# stm32_schematic.net
KiCad netlist of a schematic drawn in Altium Designer
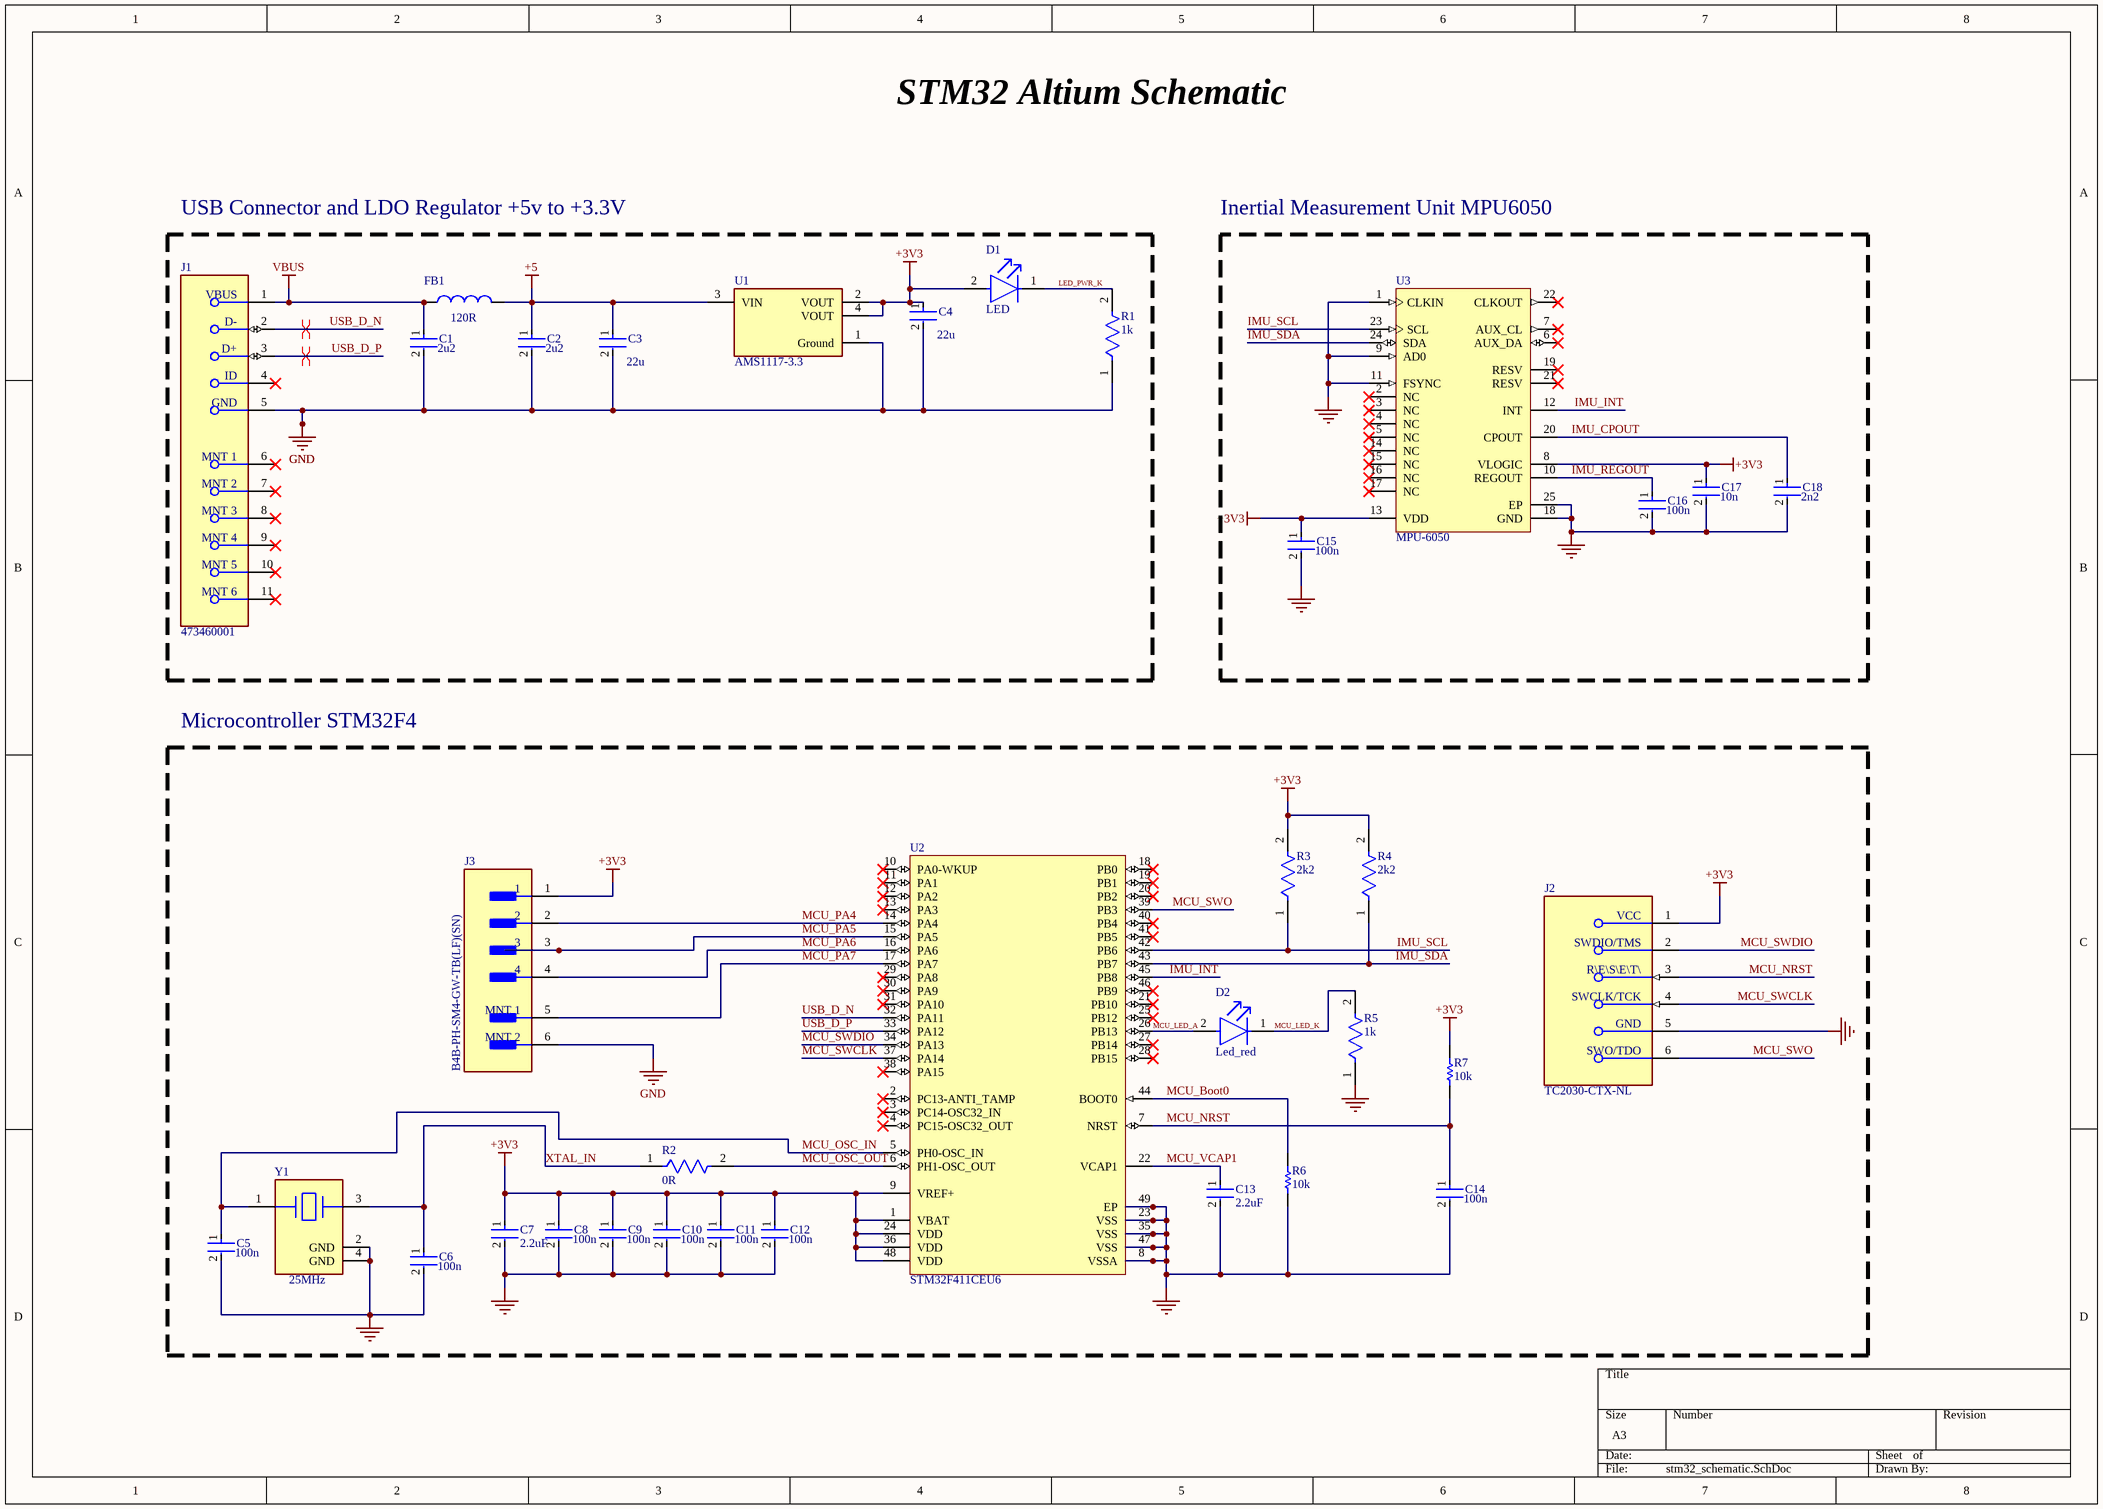
[diagram p0: stm32_schematic.SchDoc]

(export (version "E")
  (design (tool "Eeschema 10.0.6"))
  (components
    (comp (ref "C1")
      (value "2u2")
      (footprint "FP-CC0402-MFG")
      (description "CAP CER 1UF 16V X5R 0402")
      (fields
        (field (name "MANUFACTURER") "YAGEO")
        (field (name "OCTOPART") "https://octopart.com/cc0402krx5r7bb105-yageo-25629500")
      )
      (libsource (lib "Altium Content Vault") (part "11868f565c42a9108669ba33697ecf6"))
    )
    (comp (ref "C2")
      (value "2u2")
      (footprint "FP-CC0402-MFG")
      (description "CAP CER 1UF 16V X5R 0402")
      (fields
        (field (name "MANUFACTURER") "YAGEO")
        (field (name "OCTOPART") "https://octopart.com/cc0402krx5r7bb105-yageo-25629500")
      )
      (libsource (lib "Altium Content Vault") (part "11868f565c42a9108669ba33697ecf6"))
    )
    (comp (ref "C3")
      (value "22u")
      (footprint "FP-GRM21B-0_15-IPC_A")
      (description "Chip Multilayer Ceramic Capacitors for General Purpose, 0805, 4.7uF, X6S, 22%, 20%, 35V")
      (fields (field (name "TOLERANCE") "20%"))
      (libsource (lib "Altium Content Vault") (part "b4654b650e69147ec39a6b967a45e02"))
    )
    (comp (ref "C4")
      (value "22u")
      (footprint "FP-GRM21B-0_15-IPC_A")
      (description "Chip Multilayer Ceramic Capacitors for General Purpose, 0805, 4.7uF, X6S, 22%, 20%, 35V")
      (fields (field (name "TOLERANCE") "20%"))
      (libsource (lib "Altium Content Vault") (part "b4654b650e69147ec39a6b967a45e02"))
    )
    (comp (ref "C5")
      (value "100n")
      (footprint "FP-CC0402-MFG")
      (description "CAP CER 1UF 16V X5R 0402")
      (fields
        (field (name "MANUFACTURER") "YAGEO")
        (field (name "OCTOPART") "https://octopart.com/cc0402krx5r7bb105-yageo-25629500")
      )
      (libsource (lib "Altium Content Vault") (part "11868f565c42a9108669ba33697ecf6"))
    )
    (comp (ref "C6")
      (value "100n")
      (footprint "FP-CC0402-MFG")
      (description "CAP CER 1UF 16V X5R 0402")
      (fields
        (field (name "MANUFACTURER") "YAGEO")
        (field (name "OCTOPART") "https://octopart.com/cc0402krx5r7bb105-yageo-25629500")
      )
      (libsource (lib "Altium Content Vault") (part "11868f565c42a9108669ba33697ecf6"))
    )
    (comp (ref "C7")
      (value "2.2uF")
      (footprint "FP-C0603C-CF-MFG")
      (description "C0603 0.10 μF X7R 30ppm/°C 5.00% 16 V")
      (fields
        (field (name "MANUFACTURER") "KEMET")
        (field (name "OCTOPART") "https://octopart.com/c0603c104j4rac-kemet-1309211")
      )
      (libsource (lib "Altium Content Vault") (part "b4654b650e69147ec39a6b967a45e02"))
    )
    (comp (ref "C8")
      (value "100n")
      (footprint "FP-CC0402-MFG")
      (description "CAP CER 1UF 16V X5R 0402")
      (fields
        (field (name "MANUFACTURER") "YAGEO")
        (field (name "OCTOPART") "https://octopart.com/cc0402krx5r7bb105-yageo-25629500")
      )
      (libsource (lib "Altium Content Vault") (part "11868f565c42a9108669ba33697ecf6"))
    )
    (comp (ref "C9")
      (value "100n")
      (footprint "FP-CC0402-MFG")
      (description "CAP CER 1UF 16V X5R 0402")
      (fields
        (field (name "MANUFACTURER") "YAGEO")
        (field (name "OCTOPART") "https://octopart.com/cc0402krx5r7bb105-yageo-25629500")
      )
      (libsource (lib "Altium Content Vault") (part "11868f565c42a9108669ba33697ecf6"))
    )
    (comp (ref "C10")
      (value "100n")
      (footprint "FP-CC0402-MFG")
      (description "CAP CER 1UF 16V X5R 0402")
      (fields
        (field (name "MANUFACTURER") "YAGEO")
        (field (name "OCTOPART") "https://octopart.com/cc0402krx5r7bb105-yageo-25629500")
      )
      (libsource (lib "Altium Content Vault") (part "11868f565c42a9108669ba33697ecf6"))
    )
    (comp (ref "C11")
      (value "100n")
      (footprint "FP-CC0402-MFG")
      (description "CAP CER 1UF 16V X5R 0402")
      (fields
        (field (name "MANUFACTURER") "YAGEO")
        (field (name "OCTOPART") "https://octopart.com/cc0402krx5r7bb105-yageo-25629500")
      )
      (libsource (lib "Altium Content Vault") (part "11868f565c42a9108669ba33697ecf6"))
    )
    (comp (ref "C12")
      (value "100n")
      (footprint "FP-CC0402-MFG")
      (description "CAP CER 1UF 16V X5R 0402")
      (fields
        (field (name "MANUFACTURER") "YAGEO")
        (field (name "OCTOPART") "https://octopart.com/cc0402krx5r7bb105-yageo-25629500")
      )
      (libsource (lib "Altium Content Vault") (part "11868f565c42a9108669ba33697ecf6"))
    )
    (comp (ref "C13")
      (value "2.2uF")
      (footprint "FP-C0603C-CF-MFG")
      (description "C0603 0.10 μF X7R 30ppm/°C 5.00% 16 V")
      (fields
        (field (name "MANUFACTURER") "KEMET")
        (field (name "OCTOPART") "https://octopart.com/c0603c104j4rac-kemet-1309211")
      )
      (libsource (lib "Altium Content Vault") (part "b4654b650e69147ec39a6b967a45e02"))
    )
    (comp (ref "C14")
      (value "100n")
      (footprint "FP-CC0402-MFG")
      (description "CAP CER 1UF 16V X5R 0402")
      (fields
        (field (name "MANUFACTURER") "YAGEO")
        (field (name "OCTOPART") "https://octopart.com/cc0402krx5r7bb105-yageo-25629500")
      )
      (libsource (lib "Altium Content Vault") (part "11868f565c42a9108669ba33697ecf6"))
    )
    (comp (ref "C15")
      (value "100n")
      (footprint "FP-CC0402-MFG")
      (description "CAP CER 1UF 16V X5R 0402")
      (fields
        (field (name "MANUFACTURER") "YAGEO")
        (field (name "OCTOPART") "https://octopart.com/cc0402krx5r7bb105-yageo-25629500")
      )
      (libsource (lib "Altium Content Vault") (part "11868f565c42a9108669ba33697ecf6"))
    )
    (comp (ref "C16")
      (value "100n")
      (footprint "FP-CC0402-MFG")
      (description "CAP CER 1UF 16V X5R 0402")
      (fields
        (field (name "MANUFACTURER") "YAGEO")
        (field (name "OCTOPART") "https://octopart.com/cc0402krx5r7bb105-yageo-25629500")
      )
      (libsource (lib "Altium Content Vault") (part "11868f565c42a9108669ba33697ecf6"))
    )
    (comp (ref "C17")
      (value "10n")
      (footprint "FP-CC0402-MFG")
      (description "CAP CER 1UF 16V X5R 0402")
      (fields
        (field (name "MANUFACTURER") "YAGEO")
        (field (name "OCTOPART") "https://octopart.com/cc0402krx5r7bb105-yageo-25629500")
      )
      (libsource (lib "Altium Content Vault") (part "11868f565c42a9108669ba33697ecf6"))
    )
    (comp (ref "C18")
      (value "2n2")
      (footprint "FP-CC0402-MFG")
      (description "CAP CER 1UF 16V X5R 0402")
      (fields
        (field (name "MANUFACTURER") "YAGEO")
        (field (name "OCTOPART") "https://octopart.com/cc0402krx5r7bb105-yageo-25629500")
      )
      (libsource (lib "Altium Content Vault") (part "11868f565c42a9108669ba33697ecf6"))
    )
    (comp (ref "D1")
      (value "LED")
      (footprint "FP-APHHS1005CGCK-MFG")
      (description "LED GREEN CLEAR CHIP SMD")
      (libsource (lib "Altium Content Vault") (part "8706943c75ba83719d021d2fdc84c58"))
    )
    (comp (ref "D2")
      (value "Led_red")
      (footprint "FP-5988A10107F-MFG")
      (description "5988A10107F LED Uni-Color Red 2-Pin Chip 0402(1006Metric) T/R")
      (libsource (lib "Altium Content Vault") (part "8706943c75ba83719d021d2fdc84c58"))
    )
    (comp (ref "FB1")
      (value "120R")
      (footprint "WE-CBA_0805_L2W1.2H0.9_HC")
      (description "Ferrite Bead, 700 Ohm, 1.5A, 0805 Rohs Compliant: Yes")
      (libsource (lib "Altium Content Vault") (part "Ferrite"))
    )
    (comp (ref "J1")
      (value "473460001")
      (footprint "FP-473460001-MFG")
      (description "CONN RCPT USB2.0 MICRO B SMD R/A")
      (fields
        (field (name "OCTOPART") "https://octopart.com/47346-0001-molex-7164928")
        (field (name "MANUFACTURER") "Molex")
      )
      (libsource (lib "Altium Content Vault") (part "53ae1f1d9b557310b43ca686e5bb76a"))
    )
    (comp (ref "J2")
      (value "TC2030-CTX-NL")
      (footprint "FP-TC2030-CTX-NL-MFG")
      (description "6-Pin “No legs” TC2030 Plug-of-Nails™ Cable for use with ARM Cortex processors")
      (libsource (lib "Altium Content Vault") (part "e3fe093a55dc37473f431e03719485e"))
    )
    (comp (ref "J3")
      (value "B4B-PH-SM4-GW-TB(LF)(SN)")
      (footprint "FP-B4B-PH-SM4-GW-TB_LF_S-MFG")
      (description "Connector header SMT, 4 Contacts, 2A, 100V, top entry male pins")
      (libsource (lib "Altium Content Vault") (part "3b6f738a5616415d78381ad43816e4a"))
    )
    (comp (ref "R1")
      (value "1k")
      (footprint "FP-CR0402-IPC_C")
      (description "Thick Film Chip Resistors 0402 6.8Ω 0.0625W 5%")
      (fields (field (name "TOLERANCE") "5%"))
      (libsource (lib "Altium Content Vault") (part "1029c3af85768c4190bb7ad29bc67b5"))
    )
    (comp (ref "R2")
      (value "0R")
      (footprint "FP-CR0402-IPC_A")
      (description "Thick Film Chip Resistors 0402 7.68kΩ 0.0625W 1% 100ppm/°C")
      (fields (field (name "TOLERANCE") "1%"))
      (libsource (lib "Altium Content Vault") (part "1029c3af85768c4190bb7ad29bc67b5"))
    )
    (comp (ref "R3")
      (value "2k2")
      (footprint "FP-CR0402-IPC_C")
      (description "Thick Film Chip Resistors 0402 6.8Ω 0.0625W 5%")
      (fields (field (name "TOLERANCE") "5%"))
      (libsource (lib "Altium Content Vault") (part "1029c3af85768c4190bb7ad29bc67b5"))
    )
    (comp (ref "R4")
      (value "2k2")
      (footprint "FP-CR0402-IPC_C")
      (description "Thick Film Chip Resistors 0402 6.8Ω 0.0625W 5%")
      (fields (field (name "TOLERANCE") "5%"))
      (libsource (lib "Altium Content Vault") (part "1029c3af85768c4190bb7ad29bc67b5"))
    )
    (comp (ref "R5")
      (value "1k")
      (footprint "FP-CR0402-IPC_C")
      (description "Thick Film Chip Resistors 0402 6.8Ω 0.0625W 5%")
      (fields (field (name "TOLERANCE") "5%"))
      (libsource (lib "Altium Content Vault") (part "1029c3af85768c4190bb7ad29bc67b5"))
    )
    (comp (ref "R6")
      (value "10k")
      (footprint "RESC1005X37X20ML05T10")
      (fields
        (field (name "PART NUMBER") "MCS04020F2262BE100")
        (field (name "MANUFACTURER") "Vishay BCcomponents")
      )
      (libsource (lib "Altium Content Vault") (part "RES"))
    )
    (comp (ref "R7")
      (value "10k")
      (footprint "RESC1005X37X20ML05T10")
      (fields
        (field (name "PART NUMBER") "MCS04020F2262BE100")
        (field (name "MANUFACTURER") "Vishay BCcomponents")
      )
      (libsource (lib "Altium Content Vault") (part "RES"))
    )
    (comp (ref "U1")
      (value "AMS1117-3.3")
      (footprint "FP-AMS1117-IPC_C")
      (description "LDO Voltage Regulators 1A, 3.3V")
      (fields
        (field (name "OCTOPART") "https://octopart.com/ams1117-3.3-advanced+monolithic+systems-25899300")
        (field (name "MANUFACTURER") "Advanced Monolithic Systems")
      )
      (libsource (lib "Altium Content Vault") (part "8bdbb5f8e77002000e30dd2845d0354"))
    )
    (comp (ref "U2")
      (value "STM32F411CEU6")
      (footprint "STM-UFQFPN48_L")
      (libsource (lib "Altium Content Vault") (part "MC-ARM-STM32F411-UFQFPN48"))
    )
    (comp (ref "U3")
      (value "MPU-6050")
      (footprint "IS-QFN-24_V")
      (fields (field (name "MANUFACTURER") "InvenSense"))
      (libsource (lib "Altium Content Vault") (part "IS-MPU-6050-QFN-24"))
    )
    (comp (ref "Y1")
      (value "25MHz")
      (footprint "FP-ABM11AIG-MFG")
      (description "Crystal 25MHz ±30ppm 10pF SMD-4 2.5mm x 2mm Automotive")
      (libsource (lib "Altium Content Vault") (part "51b5329859b7ce12e0c2ce5858bdf70"))
    )
  )
  (nets
    (net (code "1") (name "+3V3") (class "Default")
      (node (ref "C10") (pin "1") (pinfunction "1_1") (pintype "passive"))
      (node (ref "C11") (pin "1") (pinfunction "1_1") (pintype "passive"))
      (node (ref "C12") (pin "1") (pinfunction "1_1") (pintype "passive"))
      (node (ref "C15") (pin "1") (pinfunction "1_1") (pintype "passive"))
      (node (ref "C17") (pin "1") (pinfunction "1_1") (pintype "passive"))
      (node (ref "C4") (pin "1") (pinfunction "1_1") (pintype "passive"))
      (node (ref "C7") (pin "1") (pinfunction "1_1") (pintype "passive"))
      (node (ref "C8") (pin "1") (pinfunction "1_1") (pintype "passive"))
      (node (ref "C9") (pin "1") (pinfunction "1_1") (pintype "passive"))
      (node (ref "D1") (pin "2") (pinfunction "A_2") (pintype "passive"))
      (node (ref "J2") (pin "1") (pinfunction "VCC_1") (pintype "power_in"))
      (node (ref "J3") (pin "1") (pinfunction "1_1") (pintype "passive"))
      (node (ref "R3") (pin "2") (pinfunction "2_2") (pintype "passive"))
      (node (ref "R4") (pin "2") (pinfunction "2_2") (pintype "passive"))
      (node (ref "R7") (pin "2") (pinfunction "2_2") (pintype "passive"))
      (node (ref "U1") (pin "2") (pinfunction "VOUT_2") (pintype "passive"))
      (node (ref "U1") (pin "4") (pinfunction "VOUT_4") (pintype "passive"))
      (node (ref "U2") (pin "1") (pinfunction "VBAT_1") (pintype "power_in"))
      (node (ref "U2") (pin "24") (pinfunction "VDD_24") (pintype "power_in"))
      (node (ref "U2") (pin "36") (pinfunction "VDD_36") (pintype "power_in"))
      (node (ref "U2") (pin "48") (pinfunction "VDD_48") (pintype "power_in"))
      (node (ref "U2") (pin "9") (pinfunction "VREF+_9") (pintype "power_in"))
      (node (ref "U3") (pin "13") (pinfunction "VDD_13") (pintype "power_in"))
      (node (ref "U3") (pin "8") (pinfunction "VLOGIC_8") (pintype "power_in"))
    )
    (net (code "2") (name "+5") (class "Default")
      (node (ref "C2") (pin "1") (pinfunction "1_1") (pintype "passive"))
      (node (ref "C3") (pin "1") (pinfunction "1_1") (pintype "passive"))
      (node (ref "FB1") (pin "2") (pinfunction "2_2") (pintype "passive"))
      (node (ref "U1") (pin "3") (pinfunction "VIN_3") (pintype "power_in"))
    )
    (net (code "3") (name "/IMU_CPOUT") (class "Default")
      (node (ref "C18") (pin "1") (pinfunction "1_1") (pintype "passive"))
      (node (ref "U3") (pin "20") (pinfunction "CPOUT_20") (pintype "passive"))
    )
    (net (code "4") (name "/IMU_INT") (class "Default")
      (node (ref "U2") (pin "45") (pinfunction "PB8_45") (pintype "bidirectional"))
      (node (ref "U3") (pin "12") (pinfunction "INT_12") (pintype "open_collector"))
    )
    (net (code "5") (name "/IMU_REGOUT") (class "Default")
      (node (ref "C16") (pin "1") (pinfunction "1_1") (pintype "passive"))
      (node (ref "U3") (pin "10") (pinfunction "REGOUT_10") (pintype "passive"))
    )
    (net (code "6") (name "/IMU_SCL") (class "Default")
      (node (ref "R3") (pin "1") (pinfunction "1_1") (pintype "passive"))
      (node (ref "U2") (pin "42") (pinfunction "PB6_42") (pintype "bidirectional"))
      (node (ref "U3") (pin "23") (pinfunction "SCL_23") (pintype "input"))
    )
    (net (code "7") (name "/IMU_SDA") (class "Default")
      (node (ref "R4") (pin "1") (pinfunction "1_1") (pintype "passive"))
      (node (ref "U2") (pin "43") (pinfunction "PB7_43") (pintype "bidirectional"))
      (node (ref "U3") (pin "24") (pinfunction "SDA_24") (pintype "bidirectional"))
    )
    (net (code "8") (name "/LED_PWR_K") (class "Default")
      (node (ref "D1") (pin "1") (pinfunction "C_1") (pintype "passive"))
      (node (ref "R1") (pin "2") (pinfunction "2_2") (pintype "passive"))
    )
    (net (code "9") (name "/MCU_Boot0") (class "Default")
      (node (ref "R6") (pin "2") (pinfunction "2_2") (pintype "passive"))
      (node (ref "U2") (pin "44") (pinfunction "BOOT0_44") (pintype "input"))
    )
    (net (code "10") (name "/MCU_LED_A") (class "Default")
      (node (ref "D2") (pin "2") (pinfunction "A_2") (pintype "passive"))
      (node (ref "U2") (pin "26") (pinfunction "PB13_26") (pintype "bidirectional"))
    )
    (net (code "11") (name "/MCU_LED_K") (class "Default")
      (node (ref "D2") (pin "1") (pinfunction "C_1") (pintype "passive"))
      (node (ref "R5") (pin "2") (pinfunction "2_2") (pintype "passive"))
    )
    (net (code "12") (name "/MCU_NRST") (class "Default")
      (node (ref "C14") (pin "1") (pinfunction "1_1") (pintype "passive"))
      (node (ref "J2") (pin "3") (pinfunction "~{RESET}_3") (pintype "input"))
      (node (ref "R7") (pin "1") (pinfunction "1_1") (pintype "passive"))
      (node (ref "U2") (pin "7") (pinfunction "NRST_7") (pintype "bidirectional"))
    )
    (net (code "13") (name "/MCU_OSC_IN") (class "Default")
      (node (ref "C5") (pin "1") (pinfunction "1_1") (pintype "passive"))
      (node (ref "U2") (pin "5") (pinfunction "PH0-OSC_IN_5") (pintype "bidirectional"))
      (node (ref "Y1") (pin "1") (pinfunction "1_Crystal_1") (pintype "passive"))
    )
    (net (code "14") (name "/MCU_OSC_OUT") (class "Default")
      (node (ref "R2") (pin "2") (pinfunction "2_2") (pintype "passive"))
      (node (ref "U2") (pin "6") (pinfunction "PH1-OSC_OUT_6") (pintype "bidirectional"))
    )
    (net (code "15") (name "/MCU_PA4") (class "Default")
      (node (ref "J3") (pin "2") (pinfunction "2_2") (pintype "passive"))
      (node (ref "U2") (pin "14") (pinfunction "PA4_14") (pintype "bidirectional"))
    )
    (net (code "16") (name "/MCU_PA5") (class "Default")
      (node (ref "J3") (pin "3") (pinfunction "3_3") (pintype "passive"))
      (node (ref "U2") (pin "15") (pinfunction "PA5_15") (pintype "bidirectional"))
    )
    (net (code "17") (name "/MCU_PA6") (class "Default")
      (node (ref "J3") (pin "4") (pinfunction "4_4") (pintype "passive"))
      (node (ref "U2") (pin "16") (pinfunction "PA6_16") (pintype "bidirectional"))
    )
    (net (code "18") (name "/MCU_PA7") (class "Default")
      (node (ref "J3") (pin "5") (pinfunction "MNT_1_5") (pintype "passive"))
      (node (ref "U2") (pin "17") (pinfunction "PA7_17") (pintype "bidirectional"))
    )
    (net (code "19") (name "/MCU_SWCLK") (class "Default")
      (node (ref "J2") (pin "4") (pinfunction "SWCLK/TCK_4") (pintype "input"))
      (node (ref "U2") (pin "37") (pinfunction "PA14_37") (pintype "bidirectional"))
    )
    (net (code "20") (name "/MCU_SWDIO") (class "Default")
      (node (ref "J2") (pin "2") (pinfunction "SWDIO/TMS_2") (pintype "passive"))
      (node (ref "U2") (pin "34") (pinfunction "PA13_34") (pintype "bidirectional"))
    )
    (net (code "21") (name "/MCU_SWO") (class "Default")
      (node (ref "J2") (pin "6") (pinfunction "SWO/TDO_6") (pintype "passive"))
      (node (ref "U2") (pin "39") (pinfunction "PB3_39") (pintype "bidirectional"))
    )
    (net (code "22") (name "/MCU_VCAP1") (class "Default")
      (node (ref "C13") (pin "1") (pinfunction "1_1") (pintype "passive"))
      (node (ref "U2") (pin "22") (pinfunction "VCAP1_22") (pintype "passive"))
    )
    (net (code "23") (name "/USB_D_N") (class "Default")
      (node (ref "J1") (pin "2") (pinfunction "D-_2") (pintype "bidirectional"))
      (node (ref "U2") (pin "32") (pinfunction "PA11_32") (pintype "bidirectional"))
    )
    (net (code "24") (name "/USB_D_P") (class "Default")
      (node (ref "J1") (pin "3") (pinfunction "D+_3") (pintype "bidirectional"))
      (node (ref "U2") (pin "33") (pinfunction "PA12_33") (pintype "bidirectional"))
    )
    (net (code "25") (name "/XTAL_IN") (class "Default")
      (node (ref "C6") (pin "1") (pinfunction "1_1") (pintype "passive"))
      (node (ref "R2") (pin "1") (pinfunction "1_1") (pintype "passive"))
      (node (ref "Y1") (pin "3") (pinfunction "2_Crystal_3") (pintype "passive"))
    )
    (net (code "26") (name "GND") (class "Default")
      (node (ref "C1") (pin "2") (pinfunction "2_2") (pintype "passive"))
      (node (ref "C10") (pin "2") (pinfunction "2_2") (pintype "passive"))
      (node (ref "C11") (pin "2") (pinfunction "2_2") (pintype "passive"))
      (node (ref "C12") (pin "2") (pinfunction "2_2") (pintype "passive"))
      (node (ref "C13") (pin "2") (pinfunction "2_2") (pintype "passive"))
      (node (ref "C14") (pin "2") (pinfunction "2_2") (pintype "passive"))
      (node (ref "C15") (pin "2") (pinfunction "2_2") (pintype "passive"))
      (node (ref "C16") (pin "2") (pinfunction "2_2") (pintype "passive"))
      (node (ref "C17") (pin "2") (pinfunction "2_2") (pintype "passive"))
      (node (ref "C18") (pin "2") (pinfunction "2_2") (pintype "passive"))
      (node (ref "C2") (pin "2") (pinfunction "2_2") (pintype "passive"))
      (node (ref "C3") (pin "2") (pinfunction "2_2") (pintype "passive"))
      (node (ref "C4") (pin "2") (pinfunction "2_2") (pintype "passive"))
      (node (ref "C5") (pin "2") (pinfunction "2_2") (pintype "passive"))
      (node (ref "C6") (pin "2") (pinfunction "2_2") (pintype "passive"))
      (node (ref "C7") (pin "2") (pinfunction "2_2") (pintype "passive"))
      (node (ref "C8") (pin "2") (pinfunction "2_2") (pintype "passive"))
      (node (ref "C9") (pin "2") (pinfunction "2_2") (pintype "passive"))
      (node (ref "J1") (pin "5") (pinfunction "GND_5") (pintype "power_in"))
      (node (ref "J2") (pin "5") (pinfunction "GND_5") (pintype "power_in"))
      (node (ref "J3") (pin "6") (pinfunction "MNT_2_6") (pintype "passive"))
      (node (ref "R1") (pin "1") (pinfunction "1_1") (pintype "passive"))
      (node (ref "R5") (pin "1") (pinfunction "1_1") (pintype "passive"))
      (node (ref "R6") (pin "1") (pinfunction "1_1") (pintype "passive"))
      (node (ref "U1") (pin "1") (pinfunction "Ground_1") (pintype "power_in"))
      (node (ref "U2") (pin "23") (pinfunction "VSS_23") (pintype "power_in"))
      (node (ref "U2") (pin "35") (pinfunction "VSS_35") (pintype "power_in"))
      (node (ref "U2") (pin "47") (pinfunction "VSS_47") (pintype "power_in"))
      (node (ref "U2") (pin "49") (pinfunction "EP_49") (pintype "power_in"))
      (node (ref "U2") (pin "8") (pinfunction "VSSA_8") (pintype "power_in"))
      (node (ref "U3") (pin "1") (pinfunction "CLKIN_1") (pintype "input"))
      (node (ref "U3") (pin "11") (pinfunction "FSYNC_11") (pintype "input"))
      (node (ref "U3") (pin "18") (pinfunction "GND_18") (pintype "power_in"))
      (node (ref "U3") (pin "25") (pinfunction "EP_25") (pintype "power_in"))
      (node (ref "U3") (pin "9") (pinfunction "AD0_9") (pintype "input"))
      (node (ref "Y1") (pin "2") (pinfunction "GND_2") (pintype "power_in"))
      (node (ref "Y1") (pin "4") (pinfunction "GND_4") (pintype "power_in"))
    )
    (net (code "27") (name "VBUS") (class "Default")
      (node (ref "C1") (pin "1") (pinfunction "1_1") (pintype "passive"))
      (node (ref "FB1") (pin "1") (pinfunction "1_1") (pintype "passive"))
      (node (ref "J1") (pin "1") (pinfunction "VBUS_1") (pintype "power_in"))
    )
    (net (code "28") (name "unconnected-(J1-ID-Pad4)") (class "Default")
      (node (ref "J1") (pin "4") (pinfunction "ID_4") (pintype "passive+no_connect"))
    )
    (net (code "29") (name "unconnected-(J1-MNT_1-Pad6)") (class "Default")
      (node (ref "J1") (pin "6") (pinfunction "MNT_1_6") (pintype "passive+no_connect"))
    )
    (net (code "30") (name "unconnected-(J1-MNT_2-Pad7)") (class "Default")
      (node (ref "J1") (pin "7") (pinfunction "MNT_2_7") (pintype "passive+no_connect"))
    )
    (net (code "31") (name "unconnected-(J1-MNT_3-Pad8)") (class "Default")
      (node (ref "J1") (pin "8") (pinfunction "MNT_3_8") (pintype "passive+no_connect"))
    )
    (net (code "32") (name "unconnected-(J1-MNT_4-Pad9)") (class "Default")
      (node (ref "J1") (pin "9") (pinfunction "MNT_4_9") (pintype "passive+no_connect"))
    )
    (net (code "33") (name "unconnected-(J1-MNT_5-Pad10)") (class "Default")
      (node (ref "J1") (pin "10") (pinfunction "MNT_5_10") (pintype "passive+no_connect"))
    )
    (net (code "34") (name "unconnected-(J1-MNT_6-Pad11)") (class "Default")
      (node (ref "J1") (pin "11") (pinfunction "MNT_6_11") (pintype "passive+no_connect"))
    )
    (net (code "35") (name "unconnected-(U2-PA0-WKUP-Pad10)") (class "Default")
      (node (ref "U2") (pin "10") (pinfunction "PA0-WKUP_10") (pintype "bidirectional+no_connect"))
    )
    (net (code "36") (name "unconnected-(U2-PA1-Pad11)") (class "Default")
      (node (ref "U2") (pin "11") (pinfunction "PA1_11") (pintype "bidirectional+no_connect"))
    )
    (net (code "37") (name "unconnected-(U2-PA2-Pad12)") (class "Default")
      (node (ref "U2") (pin "12") (pinfunction "PA2_12") (pintype "bidirectional+no_connect"))
    )
    (net (code "38") (name "unconnected-(U2-PA3-Pad13)") (class "Default")
      (node (ref "U2") (pin "13") (pinfunction "PA3_13") (pintype "bidirectional+no_connect"))
    )
    (net (code "39") (name "unconnected-(U2-PA8-Pad29)") (class "Default")
      (node (ref "U2") (pin "29") (pinfunction "PA8_29") (pintype "bidirectional+no_connect"))
    )
    (net (code "40") (name "unconnected-(U2-PA9-Pad30)") (class "Default")
      (node (ref "U2") (pin "30") (pinfunction "PA9_30") (pintype "bidirectional+no_connect"))
    )
    (net (code "41") (name "unconnected-(U2-PA10-Pad31)") (class "Default")
      (node (ref "U2") (pin "31") (pinfunction "PA10_31") (pintype "bidirectional+no_connect"))
    )
    (net (code "42") (name "unconnected-(U2-PA15-Pad38)") (class "Default")
      (node (ref "U2") (pin "38") (pinfunction "PA15_38") (pintype "bidirectional+no_connect"))
    )
    (net (code "43") (name "unconnected-(U2-PB0-Pad18)") (class "Default")
      (node (ref "U2") (pin "18") (pinfunction "PB0_18") (pintype "bidirectional+no_connect"))
    )
    (net (code "44") (name "unconnected-(U2-PB1-Pad19)") (class "Default")
      (node (ref "U2") (pin "19") (pinfunction "PB1_19") (pintype "bidirectional+no_connect"))
    )
    (net (code "45") (name "unconnected-(U2-PB2-Pad20)") (class "Default")
      (node (ref "U2") (pin "20") (pinfunction "PB2_20") (pintype "bidirectional+no_connect"))
    )
    (net (code "46") (name "unconnected-(U2-PB4-Pad40)") (class "Default")
      (node (ref "U2") (pin "40") (pinfunction "PB4_40") (pintype "bidirectional+no_connect"))
    )
    (net (code "47") (name "unconnected-(U2-PB5-Pad41)") (class "Default")
      (node (ref "U2") (pin "41") (pinfunction "PB5_41") (pintype "bidirectional+no_connect"))
    )
    (net (code "48") (name "unconnected-(U2-PB9-Pad46)") (class "Default")
      (node (ref "U2") (pin "46") (pinfunction "PB9_46") (pintype "bidirectional+no_connect"))
    )
    (net (code "49") (name "unconnected-(U2-PB10-Pad21)") (class "Default")
      (node (ref "U2") (pin "21") (pinfunction "PB10_21") (pintype "bidirectional+no_connect"))
    )
    (net (code "50") (name "unconnected-(U2-PB12-Pad25)") (class "Default")
      (node (ref "U2") (pin "25") (pinfunction "PB12_25") (pintype "bidirectional+no_connect"))
    )
    (net (code "51") (name "unconnected-(U2-PB14-Pad27)") (class "Default")
      (node (ref "U2") (pin "27") (pinfunction "PB14_27") (pintype "bidirectional+no_connect"))
    )
    (net (code "52") (name "unconnected-(U2-PB15-Pad28)") (class "Default")
      (node (ref "U2") (pin "28") (pinfunction "PB15_28") (pintype "bidirectional+no_connect"))
    )
    (net (code "53") (name "unconnected-(U2-PC13-ANTI_TAMP-Pad2)") (class "Default")
      (node (ref "U2") (pin "2") (pinfunction "PC13-ANTI_TAMP_2") (pintype "bidirectional+no_connect"))
    )
    (net (code "54") (name "unconnected-(U2-PC14-OSC32_IN-Pad3)") (class "Default")
      (node (ref "U2") (pin "3") (pinfunction "PC14-OSC32_IN_3") (pintype "bidirectional+no_connect"))
    )
    (net (code "55") (name "unconnected-(U2-PC15-OSC32_OUT-Pad4)") (class "Default")
      (node (ref "U2") (pin "4") (pinfunction "PC15-OSC32_OUT_4") (pintype "bidirectional+no_connect"))
    )
    (net (code "56") (name "unconnected-(U3-AUX_CL-Pad7)") (class "Default")
      (node (ref "U3") (pin "7") (pinfunction "AUX_CL_7") (pintype "output+no_connect"))
    )
    (net (code "57") (name "unconnected-(U3-AUX_DA-Pad6)") (class "Default")
      (node (ref "U3") (pin "6") (pinfunction "AUX_DA_6") (pintype "bidirectional+no_connect"))
    )
    (net (code "58") (name "unconnected-(U3-CLKOUT-Pad22)") (class "Default")
      (node (ref "U3") (pin "22") (pinfunction "CLKOUT_22") (pintype "output+no_connect"))
    )
    (net (code "59") (name "unconnected-(U3-NC-Pad2)") (class "Default")
      (node (ref "U3") (pin "2") (pinfunction "NC_2") (pintype "passive+no_connect"))
    )
    (net (code "60") (name "unconnected-(U3-NC-Pad3)") (class "Default")
      (node (ref "U3") (pin "3") (pinfunction "NC_3") (pintype "passive+no_connect"))
    )
    (net (code "61") (name "unconnected-(U3-NC-Pad4)") (class "Default")
      (node (ref "U3") (pin "4") (pinfunction "NC_4") (pintype "passive+no_connect"))
    )
    (net (code "62") (name "unconnected-(U3-NC-Pad5)") (class "Default")
      (node (ref "U3") (pin "5") (pinfunction "NC_5") (pintype "passive+no_connect"))
    )
    (net (code "63") (name "unconnected-(U3-NC-Pad14)") (class "Default")
      (node (ref "U3") (pin "14") (pinfunction "NC_14") (pintype "passive+no_connect"))
    )
    (net (code "64") (name "unconnected-(U3-NC-Pad15)") (class "Default")
      (node (ref "U3") (pin "15") (pinfunction "NC_15") (pintype "passive+no_connect"))
    )
    (net (code "65") (name "unconnected-(U3-NC-Pad16)") (class "Default")
      (node (ref "U3") (pin "16") (pinfunction "NC_16") (pintype "passive+no_connect"))
    )
    (net (code "66") (name "unconnected-(U3-NC-Pad17)") (class "Default")
      (node (ref "U3") (pin "17") (pinfunction "NC_17") (pintype "passive+no_connect"))
    )
    (net (code "67") (name "unconnected-(U3-RESV-Pad19)") (class "Default")
      (node (ref "U3") (pin "19") (pinfunction "RESV_19") (pintype "passive+no_connect"))
    )
    (net (code "68") (name "unconnected-(U3-RESV-Pad21)") (class "Default")
      (node (ref "U3") (pin "21") (pinfunction "RESV_21") (pintype "passive+no_connect"))
    )
  )
)
